# OxFloodNet_sensor.net
KiCad netlist of a schematic drawn in EAGLE
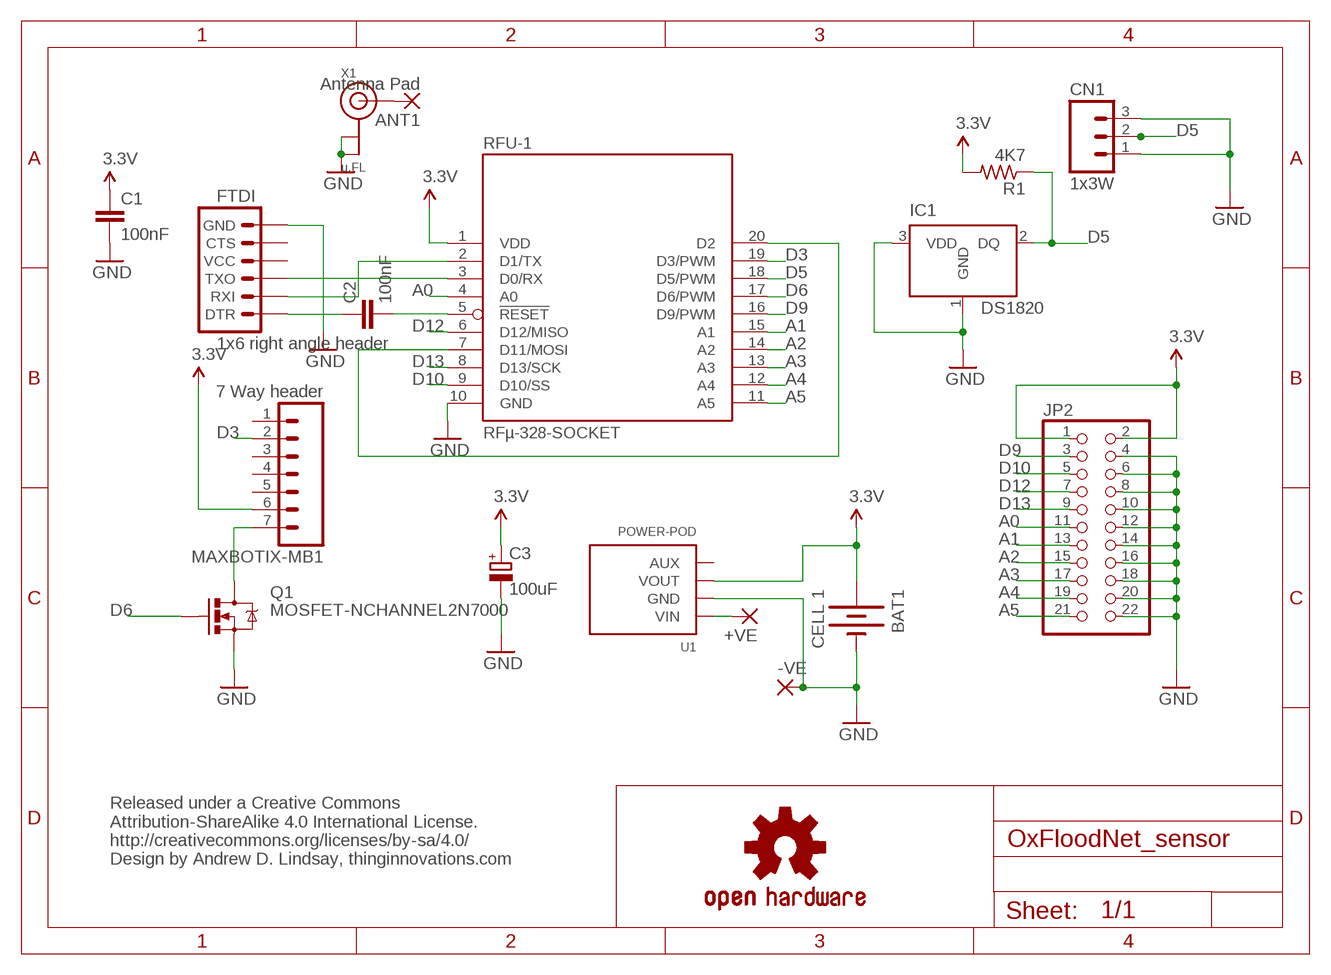
[diagram p0: schematic, sheet 1]

(export (version "E")
  (design (tool "Eeschema 10.0.6"))
  (components
    (comp (ref "+VE")
      (value "2,54/0,8")
      (footprint "eagle-import:2,54_0,8")
      (libsource (lib "eagle-import") (part "2,54/0,8"))
    )
    (comp (ref "-VE")
      (value "2,54/0,8")
      (footprint "eagle-import:2,54_0,8")
      (libsource (lib "eagle-import") (part "2,54/0,8"))
    )
    (comp (ref "ANT1")
      (value "Antenna Pad")
      (footprint "eagle-import:2,54_0,8")
      (libsource (lib "eagle-import") (part "2,54/0,8"))
    )
    (comp (ref "BAT1")
      (value "CELL 1")
      (footprint "eagle-import:BATTERY-AA")
      (libsource (lib "eagle-import") (part "BATTERYAA"))
    )
    (comp (ref "C1")
      (value "100nF")
      (footprint "eagle-import:C025-024X044")
      (libsource (lib "eagle-import") (part "C-EU025-024X044"))
    )
    (comp (ref "C2")
      (value "100nF")
      (footprint "eagle-import:C025-024X044")
      (libsource (lib "eagle-import") (part "C-EU025-024X044"))
    )
    (comp (ref "C3")
      (value "100uF")
      (footprint "eagle-import:E2,5-6E")
      (libsource (lib "eagle-import") (part "CPOL-EUE2,5-6E"))
    )
    (comp (ref "CN1")
      (value "1x3W")
      (footprint "eagle-import:1X03")
      (libsource (lib "eagle-import") (part "M03PTH"))
    )
    (comp (ref "FTDI")
      (value "1x6 right angle header")
      (footprint "eagle-import:1X06_LONGPADS")
      (libsource (lib "eagle-import") (part "ARDUINO_SERIAL_PROGRAMLONGPADS"))
    )
    (comp (ref "IC1")
      (value "DS1820")
      (footprint "eagle-import:TO-92")
      (libsource (lib "eagle-import") (part "DS1820"))
    )
    (comp (ref "JP2")
      (value "PINHD-2X11")
      (footprint "eagle-import:2X11")
      (libsource (lib "eagle-import") (part "PINHD-2X11"))
    )
    (comp (ref "LOGO1")
      (value "OSHW-LOGOM")
      (footprint "eagle-import:OSHW-LOGO-M")
      (libsource (lib "eagle-import") (part "OSHW-LOGOM"))
    )
    (comp (ref "MAXBOTIX-MB1")
      (value "7 Way header")
      (footprint "eagle-import:1X07_LONGPADS")
      (libsource (lib "eagle-import") (part "M07LONGPADS"))
    )
    (comp (ref "Q1")
      (value "MOSFET-NCHANNEL2N7000")
      (footprint "eagle-import:TO-92")
      (libsource (lib "eagle-import") (part "MOSFET-NCHANNEL2N7000"))
    )
    (comp (ref "R1")
      (value "4K7")
      (footprint "eagle-import:0207_7")
      (libsource (lib "eagle-import") (part "R-US_0207/7"))
    )
    (comp (ref "RFU-1")
      (value "RFµ-328-SOCKET")
      (footprint "eagle-import:RFµ-328-SOCKET")
      (libsource (lib "eagle-import") (part "RFµ-328-SOCKET"))
    )
    (comp (ref "U1")
      (value "POWER-POD")
      (footprint "eagle-import:POWER-POD-LANDING")
      (libsource (lib "eagle-import") (part "POWER-POD"))
    )
    (comp (ref "X1")
      (value "u.FL")
      (footprint "eagle-import:U.FL")
      (libsource (lib "eagle-import") (part "ANTENNA_U.FL"))
    )
  )
  (nets
    (net (code "1") (name "/A0") (class "Default")
      (node (ref "JP2") (pin "11") (pinfunction "11_11") (pintype "passive"))
      (node (ref "RFU-1") (pin "4") (pinfunction "A0_4") (pintype "bidirectional"))
    )
    (net (code "2") (name "/A1") (class "Default")
      (node (ref "JP2") (pin "13") (pinfunction "13_13") (pintype "passive"))
      (node (ref "RFU-1") (pin "15") (pinfunction "A1_15") (pintype "bidirectional"))
    )
    (net (code "3") (name "/A2") (class "Default")
      (node (ref "JP2") (pin "15") (pinfunction "15_15") (pintype "passive"))
      (node (ref "RFU-1") (pin "14") (pinfunction "A2_14") (pintype "bidirectional"))
    )
    (net (code "4") (name "/A3") (class "Default")
      (node (ref "JP2") (pin "17") (pinfunction "17_17") (pintype "passive"))
      (node (ref "RFU-1") (pin "13") (pinfunction "A3_13") (pintype "bidirectional"))
    )
    (net (code "5") (name "/A4") (class "Default")
      (node (ref "JP2") (pin "19") (pinfunction "19_19") (pintype "passive"))
      (node (ref "RFU-1") (pin "12") (pinfunction "A4_12") (pintype "output"))
    )
    (net (code "6") (name "/A5") (class "Default")
      (node (ref "JP2") (pin "21") (pinfunction "21_21") (pintype "passive"))
      (node (ref "RFU-1") (pin "11") (pinfunction "A5_11") (pintype "bidirectional"))
    )
    (net (code "7") (name "/D3") (class "Default")
      (node (ref "MAXBOTIX-MB1") (pin "2") (pinfunction "2_2") (pintype "passive"))
      (node (ref "RFU-1") (pin "19") (pinfunction "D3/PWM_19") (pintype "bidirectional"))
    )
    (net (code "8") (name "/D5") (class "Default")
      (node (ref "CN1") (pin "2") (pinfunction "2_2") (pintype "passive"))
      (node (ref "IC1") (pin "2") (pinfunction "DQ_2") (pintype "output"))
      (node (ref "R1") (pin "1") (pinfunction "1_1") (pintype "passive"))
      (node (ref "RFU-1") (pin "18") (pinfunction "D5/PWM_18") (pintype "bidirectional"))
    )
    (net (code "9") (name "/D6") (class "Default")
      (node (ref "Q1") (pin "2") (pinfunction "G_2") (pintype "passive"))
      (node (ref "RFU-1") (pin "17") (pinfunction "D6/PWM_17") (pintype "bidirectional"))
    )
    (net (code "10") (name "/D9") (class "Default")
      (node (ref "JP2") (pin "3") (pinfunction "3_3") (pintype "passive"))
      (node (ref "RFU-1") (pin "16") (pinfunction "D9/PWM_16") (pintype "input"))
    )
    (net (code "11") (name "/D10") (class "Default")
      (node (ref "JP2") (pin "5") (pinfunction "5_5") (pintype "passive"))
      (node (ref "RFU-1") (pin "9") (pinfunction "D10/SS_9") (pintype "bidirectional"))
    )
    (net (code "12") (name "/D12") (class "Default")
      (node (ref "JP2") (pin "7") (pinfunction "7_7") (pintype "passive"))
      (node (ref "RFU-1") (pin "6") (pinfunction "D12/MISO_6") (pintype "bidirectional"))
    )
    (net (code "13") (name "/D13") (class "Default")
      (node (ref "JP2") (pin "9") (pinfunction "9_9") (pintype "passive"))
      (node (ref "RFU-1") (pin "8") (pinfunction "D13/SCK_8") (pintype "bidirectional"))
    )
    (net (code "14") (name "3.3V") (class "Default")
      (node (ref "BAT1") (pin "PWR@1") (pinfunction "+_PWR@1") (pintype "power_in"))
      (node (ref "C1") (pin "1") (pinfunction "1_1") (pintype "passive"))
      (node (ref "C3") (pin "+") (pinfunction "+_+") (pintype "passive"))
      (node (ref "JP2") (pin "1") (pinfunction "1_1") (pintype "passive"))
      (node (ref "JP2") (pin "2") (pinfunction "2_2") (pintype "passive"))
      (node (ref "MAXBOTIX-MB1") (pin "6") (pinfunction "6_6") (pintype "passive"))
      (node (ref "R1") (pin "2") (pinfunction "2_2") (pintype "passive"))
      (node (ref "RFU-1") (pin "1") (pinfunction "VDD_1") (pintype "power_in"))
      (node (ref "U1") (pin "3") (pinfunction "VOUT_3") (pintype "bidirectional"))
    )
    (net (code "15") (name "GND") (class "Default")
      (node (ref "-VE") (pin "1") (pinfunction "P_1") (pintype "passive"))
      (node (ref "BAT1") (pin "GND@1") (pinfunction "-_GND@1") (pintype "power_in"))
      (node (ref "C1") (pin "2") (pinfunction "2_2") (pintype "passive"))
      (node (ref "C3") (pin "-") (pinfunction "-_-") (pintype "passive"))
      (node (ref "CN1") (pin "1") (pinfunction "1_1") (pintype "passive"))
      (node (ref "CN1") (pin "3") (pinfunction "3_3") (pintype "passive"))
      (node (ref "FTDI") (pin "6") (pinfunction "GND_6") (pintype "passive"))
      (node (ref "IC1") (pin "1") (pinfunction "GND_1") (pintype "power_in"))
      (node (ref "IC1") (pin "3") (pinfunction "VDD_3") (pintype "input"))
      (node (ref "JP2") (pin "10") (pinfunction "10_10") (pintype "passive"))
      (node (ref "JP2") (pin "12") (pinfunction "12_12") (pintype "passive"))
      (node (ref "JP2") (pin "14") (pinfunction "14_14") (pintype "passive"))
      (node (ref "JP2") (pin "16") (pinfunction "16_16") (pintype "passive"))
      (node (ref "JP2") (pin "18") (pinfunction "18_18") (pintype "passive"))
      (node (ref "JP2") (pin "20") (pinfunction "20_20") (pintype "passive"))
      (node (ref "JP2") (pin "22") (pinfunction "22_22") (pintype "passive"))
      (node (ref "JP2") (pin "4") (pinfunction "4_4") (pintype "passive"))
      (node (ref "JP2") (pin "6") (pinfunction "6_6") (pintype "passive"))
      (node (ref "JP2") (pin "8") (pinfunction "8_8") (pintype "passive"))
      (node (ref "Q1") (pin "1") (pinfunction "S_1") (pintype "passive"))
      (node (ref "RFU-1") (pin "10") (pinfunction "GND_10") (pintype "power_in"))
      (node (ref "U1") (pin "2") (pinfunction "GND_2") (pintype "bidirectional"))
      (node (ref "X1") (pin "1") (pinfunction "GND_1") (pintype "passive"))
      (node (ref "X1") (pin "2") (pinfunction "GND_2") (pintype "passive"))
    )
    (net (code "16") (name "Net-(+VE-P)") (class "Default")
      (node (ref "+VE") (pin "1") (pinfunction "P_1") (pintype "passive"))
      (node (ref "U1") (pin "1") (pinfunction "VIN_1") (pintype "bidirectional"))
    )
    (net (code "17") (name "Net-(ANT1-P)") (class "Default")
      (node (ref "ANT1") (pin "1") (pinfunction "P_1") (pintype "passive"))
      (node (ref "X1") (pin "3") (pinfunction "SIGNAL_3") (pintype "passive"))
    )
    (net (code "18") (name "Net-(FTDI-DTR)") (class "Default")
      (node (ref "C2") (pin "1") (pinfunction "1_1") (pintype "passive"))
      (node (ref "FTDI") (pin "1") (pinfunction "DTR_1") (pintype "passive"))
    )
    (net (code "19") (name "Net-(FTDI-RXI)") (class "Default")
      (node (ref "FTDI") (pin "2") (pinfunction "RXI_2") (pintype "passive"))
      (node (ref "RFU-1") (pin "2") (pinfunction "D1/TX_2") (pintype "output"))
    )
    (net (code "20") (name "Net-(FTDI-TXO)") (class "Default")
      (node (ref "FTDI") (pin "3") (pinfunction "TXO_3") (pintype "passive"))
      (node (ref "RFU-1") (pin "3") (pinfunction "D0/RX_3") (pintype "input"))
    )
    (net (code "21") (name "Net-(Q1-D)") (class "Default")
      (node (ref "MAXBOTIX-MB1") (pin "7") (pinfunction "7_7") (pintype "passive"))
      (node (ref "Q1") (pin "3") (pinfunction "D_3") (pintype "passive"))
    )
    (net (code "22") (name "Net-(RFU-1-D11{slash}MOSI)") (class "Default")
      (node (ref "RFU-1") (pin "20") (pinfunction "D2_20") (pintype "bidirectional"))
      (node (ref "RFU-1") (pin "7") (pinfunction "D11/MOSI_7") (pintype "bidirectional"))
    )
    (net (code "23") (name "Net-(RFU-1-~{RESET})") (class "Default")
      (node (ref "C2") (pin "2") (pinfunction "2_2") (pintype "passive"))
      (node (ref "RFU-1") (pin "5") (pinfunction "~{RESET}_5") (pintype "input"))
    )
    (net (code "24") (name "unconnected-(FTDI-CTS-Pad5)") (class "Default")
      (node (ref "FTDI") (pin "5") (pinfunction "CTS_5") (pintype "passive"))
    )
    (net (code "25") (name "unconnected-(FTDI-VCC-Pad4)") (class "Default")
      (node (ref "FTDI") (pin "4") (pinfunction "VCC_4") (pintype "passive"))
    )
    (net (code "26") (name "unconnected-(MAXBOTIX-MB1-Pad1)") (class "Default")
      (node (ref "MAXBOTIX-MB1") (pin "1") (pinfunction "1_1") (pintype "passive"))
    )
    (net (code "27") (name "unconnected-(MAXBOTIX-MB1-Pad3)") (class "Default")
      (node (ref "MAXBOTIX-MB1") (pin "3") (pinfunction "3_3") (pintype "passive"))
    )
    (net (code "28") (name "unconnected-(MAXBOTIX-MB1-Pad4)") (class "Default")
      (node (ref "MAXBOTIX-MB1") (pin "4") (pinfunction "4_4") (pintype "passive"))
    )
    (net (code "29") (name "unconnected-(MAXBOTIX-MB1-Pad5)") (class "Default")
      (node (ref "MAXBOTIX-MB1") (pin "5") (pinfunction "5_5") (pintype "passive"))
    )
    (net (code "30") (name "unconnected-(U1-AUX-Pad4)") (class "Default")
      (node (ref "U1") (pin "4") (pinfunction "AUX_4") (pintype "bidirectional"))
    )
  )
)
